# 297-298.net
KiCad netlist of a schematic drawn in EAGLE
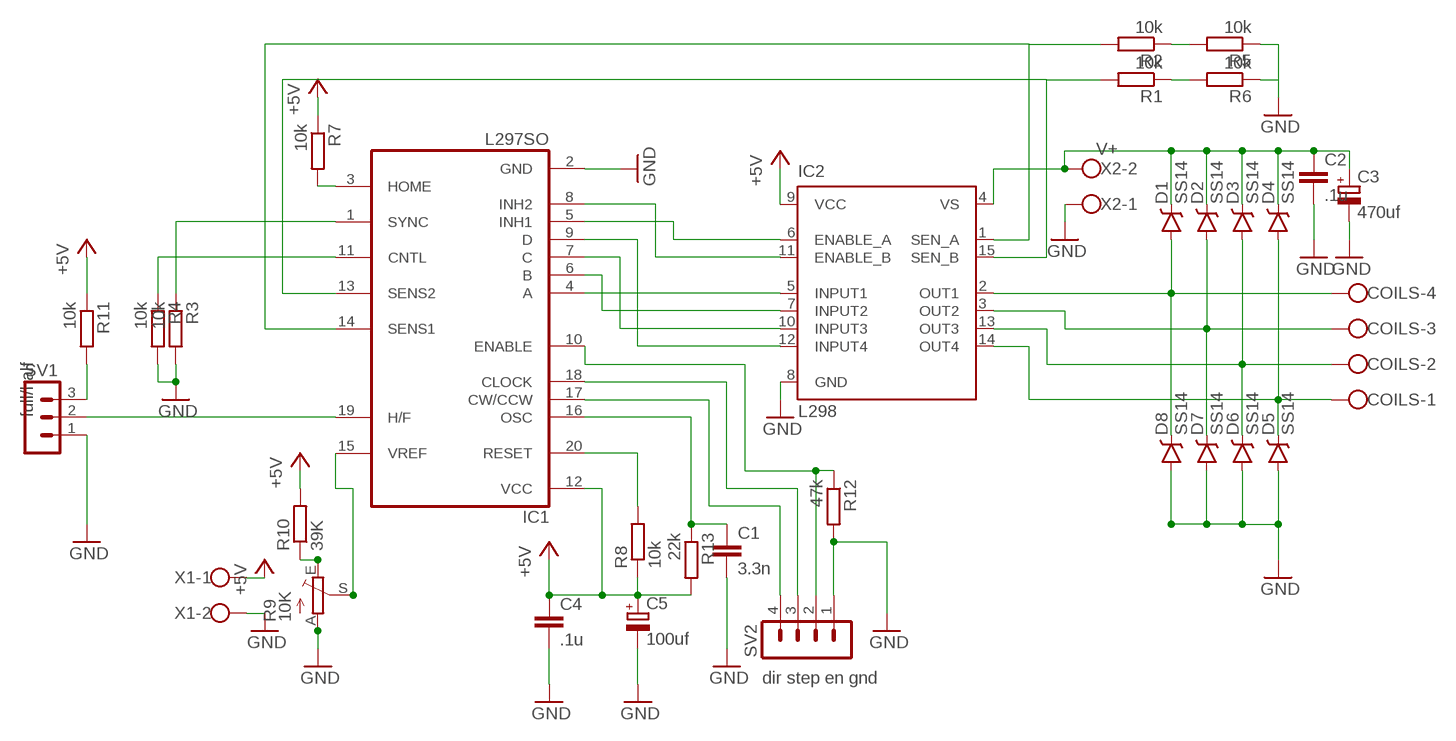
[diagram p0: schematic, sheet 1]

(export (version "E")
  (design (tool "Eeschema 10.0.6"))
  (components
    (comp (ref "C1")
      (value "3.3n")
      (footprint "eagle-import:C0805")
      (libsource (lib "eagle-import") (part "CC0805"))
    )
    (comp (ref "C2")
      (value ".1u")
      (footprint "eagle-import:C0805")
      (libsource (lib "eagle-import") (part "CC0805"))
    )
    (comp (ref "C3")
      (value "470uf")
      (footprint "eagle-import:E3,5-8")
      (libsource (lib "eagle-import") (part "CPOL-EUE3.5-8"))
    )
    (comp (ref "C4")
      (value ".1u")
      (footprint "eagle-import:C0805")
      (libsource (lib "eagle-import") (part "CC0805"))
    )
    (comp (ref "C5")
      (value "100uf")
      (footprint "eagle-import:E3,5-8")
      (libsource (lib "eagle-import") (part "CPOL-EUE3.5-8"))
    )
    (comp (ref "COILS")
      (value "W237-4")
      (footprint "eagle-import:W237-4")
      (libsource (lib "eagle-import") (part "W237-4"))
    )
    (comp (ref "D1")
      (value "SS14")
      (footprint "eagle-import:SMA-DIODE")
      (libsource (lib "eagle-import") (part "SS14"))
    )
    (comp (ref "D2")
      (value "SS14")
      (footprint "eagle-import:SMA-DIODE")
      (libsource (lib "eagle-import") (part "SS14"))
    )
    (comp (ref "D3")
      (value "SS14")
      (footprint "eagle-import:SMA-DIODE")
      (libsource (lib "eagle-import") (part "SS14"))
    )
    (comp (ref "D4")
      (value "SS14")
      (footprint "eagle-import:SMA-DIODE")
      (libsource (lib "eagle-import") (part "SS14"))
    )
    (comp (ref "D5")
      (value "SS14")
      (footprint "eagle-import:SMA-DIODE")
      (libsource (lib "eagle-import") (part "SS14"))
    )
    (comp (ref "D6")
      (value "SS14")
      (footprint "eagle-import:SMA-DIODE")
      (libsource (lib "eagle-import") (part "SS14"))
    )
    (comp (ref "D7")
      (value "SS14")
      (footprint "eagle-import:SMA-DIODE")
      (libsource (lib "eagle-import") (part "SS14"))
    )
    (comp (ref "D8")
      (value "SS14")
      (footprint "eagle-import:SMA-DIODE")
      (libsource (lib "eagle-import") (part "SS14"))
    )
    (comp (ref "IC1")
      (value "L297SO")
      (footprint "eagle-import:SO20")
      (libsource (lib "eagle-import") (part "L297SO"))
    )
    (comp (ref "IC2")
      (value "L298")
      (footprint "eagle-import:MULTIWATT-15")
      (fields (field (name "MPN") "L298N"))
      (libsource (lib "eagle-import") (part "L298"))
    )
    (comp (ref "R1")
      (value "10k")
      (footprint "eagle-import:R2512")
      (libsource (lib "eagle-import") (part "R2512"))
    )
    (comp (ref "R2")
      (value "10k")
      (footprint "eagle-import:R2512")
      (libsource (lib "eagle-import") (part "R2512"))
    )
    (comp (ref "R3")
      (value "10k")
      (footprint "eagle-import:R0805")
      (libsource (lib "eagle-import") (part "R0805"))
    )
    (comp (ref "R4")
      (value "10k")
      (footprint "eagle-import:R0805")
      (libsource (lib "eagle-import") (part "R0805"))
    )
    (comp (ref "R5")
      (value "10k")
      (footprint "eagle-import:R2512")
      (libsource (lib "eagle-import") (part "R2512"))
    )
    (comp (ref "R6")
      (value "10k")
      (footprint "eagle-import:R2512")
      (libsource (lib "eagle-import") (part "R2512"))
    )
    (comp (ref "R7")
      (value "10k")
      (footprint "eagle-import:R0805")
      (libsource (lib "eagle-import") (part "R0805"))
    )
    (comp (ref "R8")
      (value "10k")
      (footprint "eagle-import:R0805")
      (libsource (lib "eagle-import") (part "R0805"))
    )
    (comp (ref "R9")
      (value "10K")
      (footprint "eagle-import:CA9V")
      (libsource (lib "eagle-import") (part "TRIM_EU-CA9V"))
    )
    (comp (ref "R10")
      (value "39K")
      (footprint "eagle-import:R0805")
      (libsource (lib "eagle-import") (part "R0805"))
    )
    (comp (ref "R11")
      (value "10k")
      (footprint "eagle-import:R0805")
      (libsource (lib "eagle-import") (part "R0805"))
    )
    (comp (ref "R12")
      (value "47k")
      (footprint "eagle-import:R0805")
      (libsource (lib "eagle-import") (part "R0805"))
    )
    (comp (ref "R13")
      (value "22k")
      (footprint "eagle-import:R0805")
      (libsource (lib "eagle-import") (part "R0805"))
    )
    (comp (ref "SV1")
      (value "MA03-1")
      (footprint "eagle-import:MA03-1")
      (libsource (lib "eagle-import") (part "MA03-1"))
    )
    (comp (ref "SV2")
      (value "MA04-1")
      (footprint "eagle-import:MA04-1")
      (libsource (lib "eagle-import") (part "MA04-1"))
    )
    (comp (ref "X1")
      (value "W237-102")
      (footprint "eagle-import:W237-102")
      (fields (field (name "MPN") "237-102"))
      (libsource (lib "eagle-import") (part "W237-102"))
    )
    (comp (ref "X2")
      (value "V+")
      (footprint "eagle-import:W237-102")
      (fields (field (name "MPN") "237-102"))
      (libsource (lib "eagle-import") (part "W237-102"))
    )
  )
  (nets
    (net (code "1") (name "+5V") (class "Default")
      (node (ref "C4") (pin "1") (pinfunction "1_1") (pintype "passive"))
      (node (ref "C5") (pin "+") (pinfunction "+_+") (pintype "passive"))
      (node (ref "IC1") (pin "12") (pinfunction "VCC_12") (pintype "power_in"))
      (node (ref "IC2") (pin "9") (pinfunction "VCC_9") (pintype "power_in"))
      (node (ref "R10") (pin "2") (pinfunction "2_2") (pintype "passive"))
      (node (ref "R11") (pin "1") (pinfunction "1_1") (pintype "passive"))
      (node (ref "R13") (pin "2") (pinfunction "2_2") (pintype "passive"))
      (node (ref "R7") (pin "1") (pinfunction "1_1") (pintype "passive"))
      (node (ref "R8") (pin "1") (pinfunction "1_1") (pintype "passive"))
      (node (ref "X1") (pin "1") (pinfunction "KL_1") (pintype "passive"))
    )
    (net (code "2") (name "GND") (class "Default")
      (node (ref "C1") (pin "2") (pinfunction "2_2") (pintype "passive"))
      (node (ref "C2") (pin "2") (pinfunction "2_2") (pintype "passive"))
      (node (ref "C3") (pin "-") (pinfunction "-_-") (pintype "passive"))
      (node (ref "C4") (pin "2") (pinfunction "2_2") (pintype "passive"))
      (node (ref "C5") (pin "-") (pinfunction "-_-") (pintype "passive"))
      (node (ref "D5") (pin "A") (pinfunction "A_A") (pintype "passive"))
      (node (ref "D6") (pin "A") (pinfunction "A_A") (pintype "passive"))
      (node (ref "D7") (pin "A") (pinfunction "A_A") (pintype "passive"))
      (node (ref "D8") (pin "A") (pinfunction "A_A") (pintype "passive"))
      (node (ref "IC1") (pin "2") (pinfunction "GND_2") (pintype "power_in"))
      (node (ref "IC2") (pin "8") (pinfunction "GND_8") (pintype "power_in"))
      (node (ref "R12") (pin "2") (pinfunction "2_2") (pintype "passive"))
      (node (ref "R3") (pin "2") (pinfunction "2_2") (pintype "passive"))
      (node (ref "R4") (pin "2") (pinfunction "2_2") (pintype "passive"))
      (node (ref "R5") (pin "P$1") (pinfunction "1_P$1") (pintype "passive"))
      (node (ref "R6") (pin "P$1") (pinfunction "1_P$1") (pintype "passive"))
      (node (ref "R9") (pin "A") (pinfunction "A_A") (pintype "passive"))
      (node (ref "SV1") (pin "1") (pinfunction "1_1") (pintype "passive"))
      (node (ref "SV2") (pin "1") (pinfunction "1_1") (pintype "passive"))
      (node (ref "X1") (pin "2") (pinfunction "KL_2") (pintype "passive"))
      (node (ref "X2") (pin "1") (pinfunction "KL_1") (pintype "passive"))
    )
    (net (code "3") (name "Net-(COILSA-KL)") (class "Default")
      (node (ref "COILS") (pin "1") (pinfunction "KL_1") (pintype "passive"))
      (node (ref "D4") (pin "A") (pinfunction "A_A") (pintype "passive"))
      (node (ref "D5") (pin "C") (pinfunction "C_C") (pintype "passive"))
      (node (ref "IC2") (pin "14") (pinfunction "OUT4_14") (pintype "output"))
    )
    (net (code "4") (name "Net-(COILSB-KL)") (class "Default")
      (node (ref "COILS") (pin "2") (pinfunction "KL_2") (pintype "passive"))
      (node (ref "D3") (pin "A") (pinfunction "A_A") (pintype "passive"))
      (node (ref "D6") (pin "C") (pinfunction "C_C") (pintype "passive"))
      (node (ref "IC2") (pin "13") (pinfunction "OUT3_13") (pintype "output"))
    )
    (net (code "5") (name "Net-(COILSC-KL)") (class "Default")
      (node (ref "COILS") (pin "3") (pinfunction "KL_3") (pintype "passive"))
      (node (ref "D2") (pin "A") (pinfunction "A_A") (pintype "passive"))
      (node (ref "D7") (pin "C") (pinfunction "C_C") (pintype "passive"))
      (node (ref "IC2") (pin "3") (pinfunction "OUT2_3") (pintype "output"))
    )
    (net (code "6") (name "Net-(COILSD-KL)") (class "Default")
      (node (ref "COILS") (pin "4") (pinfunction "KL_4") (pintype "passive"))
      (node (ref "D1") (pin "A") (pinfunction "A_A") (pintype "passive"))
      (node (ref "D8") (pin "C") (pinfunction "C_C") (pintype "passive"))
      (node (ref "IC2") (pin "2") (pinfunction "OUT1_2") (pintype "output"))
    )
    (net (code "7") (name "Net-(IC1-A)") (class "Default")
      (node (ref "IC1") (pin "4") (pinfunction "A_4") (pintype "output"))
      (node (ref "IC2") (pin "5") (pinfunction "INPUT1_5") (pintype "input"))
    )
    (net (code "8") (name "Net-(IC1-B)") (class "Default")
      (node (ref "IC1") (pin "6") (pinfunction "B_6") (pintype "output"))
      (node (ref "IC2") (pin "7") (pinfunction "INPUT2_7") (pintype "input"))
    )
    (net (code "9") (name "Net-(IC1-C)") (class "Default")
      (node (ref "IC1") (pin "7") (pinfunction "C_7") (pintype "output"))
      (node (ref "IC2") (pin "10") (pinfunction "INPUT3_10") (pintype "input"))
    )
    (net (code "10") (name "Net-(IC1-CLOCK)") (class "Default")
      (node (ref "IC1") (pin "18") (pinfunction "CLOCK_18") (pintype "input"))
      (node (ref "SV2") (pin "3") (pinfunction "3_3") (pintype "passive"))
    )
    (net (code "11") (name "Net-(IC1-CNTL)") (class "Default")
      (node (ref "IC1") (pin "11") (pinfunction "CNTL_11") (pintype "input"))
      (node (ref "R4") (pin "1") (pinfunction "1_1") (pintype "passive"))
    )
    (net (code "12") (name "Net-(IC1-CW{slash}CCW)") (class "Default")
      (node (ref "IC1") (pin "17") (pinfunction "CW/CCW_17") (pintype "input"))
      (node (ref "SV2") (pin "4") (pinfunction "4_4") (pintype "passive"))
    )
    (net (code "13") (name "Net-(IC1-D)") (class "Default")
      (node (ref "IC1") (pin "9") (pinfunction "D_9") (pintype "output"))
      (node (ref "IC2") (pin "12") (pinfunction "INPUT4_12") (pintype "input"))
    )
    (net (code "14") (name "Net-(IC1-ENABLE)") (class "Default")
      (node (ref "IC1") (pin "10") (pinfunction "ENABLE_10") (pintype "input"))
      (node (ref "R12") (pin "1") (pinfunction "1_1") (pintype "passive"))
      (node (ref "SV2") (pin "2") (pinfunction "2_2") (pintype "passive"))
    )
    (net (code "15") (name "Net-(IC1-HOME)") (class "Default")
      (node (ref "IC1") (pin "3") (pinfunction "HOME_3") (pintype "output"))
      (node (ref "R7") (pin "2") (pinfunction "2_2") (pintype "passive"))
    )
    (net (code "16") (name "Net-(IC1-H{slash}F)") (class "Default")
      (node (ref "IC1") (pin "19") (pinfunction "H/F_19") (pintype "input"))
      (node (ref "SV1") (pin "2") (pinfunction "2_2") (pintype "passive"))
    )
    (net (code "17") (name "Net-(IC1-INH1)") (class "Default")
      (node (ref "IC1") (pin "5") (pinfunction "INH1_5") (pintype "output"))
      (node (ref "IC2") (pin "6") (pinfunction "ENABLE_A_6") (pintype "input"))
    )
    (net (code "18") (name "Net-(IC1-INH2)") (class "Default")
      (node (ref "IC1") (pin "8") (pinfunction "INH2_8") (pintype "output"))
      (node (ref "IC2") (pin "11") (pinfunction "ENABLE_B_11") (pintype "input"))
    )
    (net (code "19") (name "Net-(IC1-OSC)") (class "Default")
      (node (ref "C1") (pin "1") (pinfunction "1_1") (pintype "passive"))
      (node (ref "IC1") (pin "16") (pinfunction "OSC_16") (pintype "bidirectional"))
      (node (ref "R13") (pin "1") (pinfunction "1_1") (pintype "passive"))
    )
    (net (code "20") (name "Net-(IC1-RESET)") (class "Default")
      (node (ref "IC1") (pin "20") (pinfunction "RESET_20") (pintype "input"))
      (node (ref "R8") (pin "2") (pinfunction "2_2") (pintype "passive"))
    )
    (net (code "21") (name "Net-(IC1-SENS1)") (class "Default")
      (node (ref "IC1") (pin "14") (pinfunction "SENS1_14") (pintype "output"))
      (node (ref "IC2") (pin "1") (pinfunction "SEN_A_1") (pintype "input"))
      (node (ref "R2") (pin "P$2") (pinfunction "2_P$2") (pintype "passive"))
    )
    (net (code "22") (name "Net-(IC1-SENS2)") (class "Default")
      (node (ref "IC1") (pin "13") (pinfunction "SENS2_13") (pintype "output"))
      (node (ref "IC2") (pin "15") (pinfunction "SEN_B_15") (pintype "input"))
      (node (ref "R1") (pin "P$2") (pinfunction "2_P$2") (pintype "passive"))
    )
    (net (code "23") (name "Net-(IC1-SYNC)") (class "Default")
      (node (ref "IC1") (pin "1") (pinfunction "SYNC_1") (pintype "output"))
      (node (ref "R3") (pin "1") (pinfunction "1_1") (pintype "passive"))
    )
    (net (code "24") (name "Net-(IC1-VREF)") (class "Default")
      (node (ref "IC1") (pin "15") (pinfunction "VREF_15") (pintype "input"))
      (node (ref "R9") (pin "S") (pinfunction "S_S") (pintype "passive"))
    )
    (net (code "25") (name "Net-(IC2-VS)") (class "Default")
      (node (ref "C2") (pin "1") (pinfunction "1_1") (pintype "passive"))
      (node (ref "C3") (pin "+") (pinfunction "+_+") (pintype "passive"))
      (node (ref "D1") (pin "C") (pinfunction "C_C") (pintype "passive"))
      (node (ref "D2") (pin "C") (pinfunction "C_C") (pintype "passive"))
      (node (ref "D3") (pin "C") (pinfunction "C_C") (pintype "passive"))
      (node (ref "D4") (pin "C") (pinfunction "C_C") (pintype "passive"))
      (node (ref "IC2") (pin "4") (pinfunction "VS_4") (pintype "power_in"))
      (node (ref "X2") (pin "2") (pinfunction "KL_2") (pintype "passive"))
    )
    (net (code "26") (name "Net-(R1-1)") (class "Default")
      (node (ref "R1") (pin "P$1") (pinfunction "1_P$1") (pintype "passive"))
      (node (ref "R6") (pin "P$2") (pinfunction "2_P$2") (pintype "passive"))
    )
    (net (code "27") (name "Net-(R2-1)") (class "Default")
      (node (ref "R2") (pin "P$1") (pinfunction "1_P$1") (pintype "passive"))
      (node (ref "R5") (pin "P$2") (pinfunction "2_P$2") (pintype "passive"))
    )
    (net (code "28") (name "Net-(R10-Pad1)") (class "Default")
      (node (ref "R10") (pin "1") (pinfunction "1_1") (pintype "passive"))
      (node (ref "R9") (pin "E") (pinfunction "E_E") (pintype "passive"))
    )
    (net (code "29") (name "Net-(R11-Pad2)") (class "Default")
      (node (ref "R11") (pin "2") (pinfunction "2_2") (pintype "passive"))
      (node (ref "SV1") (pin "3") (pinfunction "3_3") (pintype "passive"))
    )
  )
)
